# maus-blenano2-mk-1_1_0.net
KiCad netlist of a schematic drawn in EAGLE
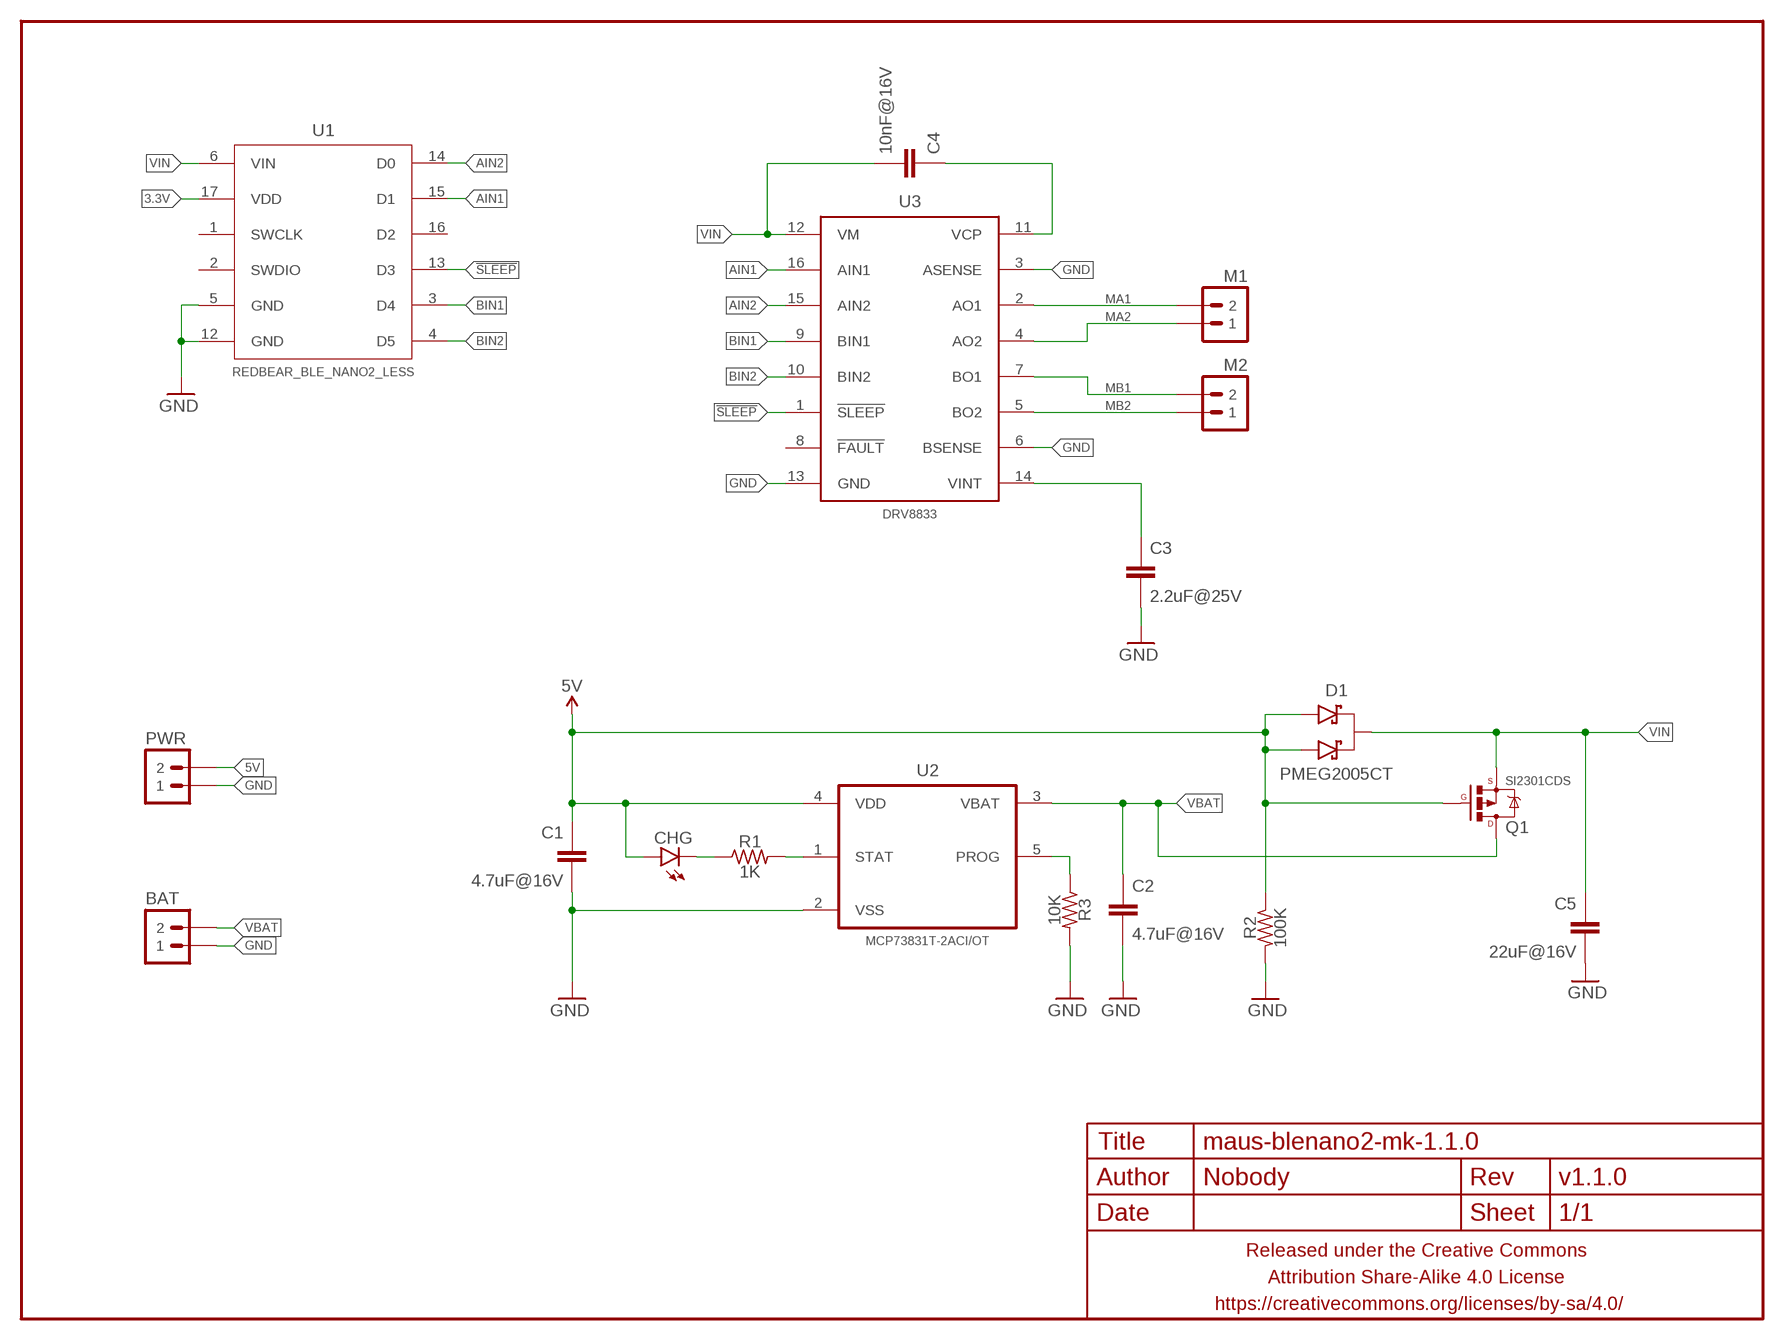
[diagram p0: schematic, sheet 1]

(export (version "E")
  (design (tool "Eeschema 10.0.6"))
  (components
    (comp (ref "BAT")
      (value "M02PTH-2MM")
      (footprint "eagle-import:1X02-2MM-PTH")
      (libsource (lib "eagle-import") (part "M02PTH-2MM"))
    )
    (comp (ref "C1")
      (value "4.7uF@16V")
      (footprint "eagle-import:C0603-TIGHTER")
      (libsource (lib "eagle-import") (part "CAPACITOR-CERAMICC0603-TIGHTER"))
    )
    (comp (ref "C2")
      (value "4.7uF@16V")
      (footprint "eagle-import:C0603-TIGHTER")
      (libsource (lib "eagle-import") (part "CAPACITOR-CERAMICC0603-TIGHTER"))
    )
    (comp (ref "C3")
      (value "2.2uF@25V")
      (footprint "eagle-import:C0603")
      (libsource (lib "eagle-import") (part "CAPACITOR-CERAMICC0603"))
    )
    (comp (ref "C4")
      (value "10nF@16V")
      (footprint "eagle-import:C0402")
      (libsource (lib "eagle-import") (part "CAPACITOR-CERAMICC0402"))
    )
    (comp (ref "C5")
      (value "22uF@16V")
      (footprint "eagle-import:C1206")
      (libsource (lib "eagle-import") (part "CAPACITOR-CERAMICC1206"))
    )
    (comp (ref "CHG")
      (value "LED0603-TIGHT")
      (footprint "eagle-import:LED-0603-TIGHT")
      (libsource (lib "eagle-import") (part "LED0603-TIGHT"))
    )
    (comp (ref "D1")
      (value "PMEG2005CT")
      (footprint "eagle-import:SOT23")
      (libsource (lib "eagle-import") (part "DIODE-SCHOTTKY-DUALPMEG2005CT"))
    )
    (comp (ref "FRAME1")
      (value "FRAME-LETTERNO_PACKAGE")
      (footprint "eagle-import:DUMMY")
      (fields (field (name "VERSION") "v1.1.0") (field (name "DESIGNER") "Nobody"))
      (libsource (lib "eagle-import") (part "FRAME-LETTERNO_PACKAGE"))
    )
    (comp (ref "M1")
      (value "M02PTH-2MM")
      (footprint "eagle-import:1X02-2MM-PTH")
      (libsource (lib "eagle-import") (part "M02PTH-2MM"))
    )
    (comp (ref "M2")
      (value "M02PTH-2MM")
      (footprint "eagle-import:1X02-2MM-PTH")
      (libsource (lib "eagle-import") (part "M02PTH-2MM"))
    )
    (comp (ref "PWR")
      (value "M02PTH-2MM")
      (footprint "eagle-import:1X02-2MM-PTH")
      (libsource (lib "eagle-import") (part "M02PTH-2MM"))
    )
    (comp (ref "Q1")
      (value "SI2301CDS")
      (footprint "eagle-import:SOT23")
      (libsource (lib "eagle-import") (part "MOSFET-PCHANNELSOT-23"))
    )
    (comp (ref "R1")
      (value "1K")
      (footprint "eagle-import:R0603-TIGHTER")
      (libsource (lib "eagle-import") (part "RESISTORR0603-TIGHTER"))
    )
    (comp (ref "R2")
      (value "100K")
      (footprint "eagle-import:R0603-TIGHTER")
      (libsource (lib "eagle-import") (part "RESISTORR0603-TIGHTER"))
    )
    (comp (ref "R3")
      (value "10K")
      (footprint "eagle-import:R0603-TIGHTER")
      (libsource (lib "eagle-import") (part "RESISTORR0603-TIGHTER"))
    )
    (comp (ref "U1")
      (value "REDBEAR_BLE_NANO2_LESS")
      (footprint "eagle-import:REDBEAR_BLE_NANO2_LESS")
      (libsource (lib "eagle-import") (part "REDBEAR_BLE_NANO2_LESS"))
    )
    (comp (ref "U2")
      (value "MCP73831T-2ACI/OT")
      (footprint "eagle-import:SOT95P280X145-5N")
      (libsource (lib "eagle-import") (part "MCP73831T-2ACI/OT"))
    )
    (comp (ref "U3")
      (value "DRV8833")
      (footprint "eagle-import:TSSOP16")
      (libsource (lib "eagle-import") (part "DRV8833PW"))
    )
  )
  (nets
    (net (code "1") (name "/MA1") (class "Default")
      (node (ref "M1") (pin "P$2") (pinfunction "2_P$2") (pintype "passive"))
      (node (ref "U3") (pin "2") (pinfunction "AO1_2") (pintype "bidirectional"))
    )
    (net (code "2") (name "/MA2") (class "Default")
      (node (ref "M1") (pin "P$1") (pinfunction "1_P$1") (pintype "passive"))
      (node (ref "U3") (pin "4") (pinfunction "AO2_4") (pintype "bidirectional"))
    )
    (net (code "3") (name "/MB1") (class "Default")
      (node (ref "M2") (pin "P$2") (pinfunction "2_P$2") (pintype "passive"))
      (node (ref "U3") (pin "7") (pinfunction "BO1_7") (pintype "bidirectional"))
    )
    (net (code "4") (name "/MB2") (class "Default")
      (node (ref "M2") (pin "P$1") (pinfunction "1_P$1") (pintype "passive"))
      (node (ref "U3") (pin "5") (pinfunction "BO2_5") (pintype "bidirectional"))
    )
    (net (code "5") (name "/~{SLEEP}") (class "Default")
      (node (ref "U1") (pin "13") (pinfunction "D3_13") (pintype "bidirectional"))
      (node (ref "U3") (pin "1") (pinfunction "~{SLEEP}_1") (pintype "input"))
    )
    (net (code "6") (name "3.3V") (class "Default")
      (node (ref "U1") (pin "17") (pinfunction "VDD_17") (pintype "bidirectional"))
    )
    (net (code "7") (name "5V") (class "Default")
      (node (ref "C1") (pin "1") (pinfunction "1_1") (pintype "passive"))
      (node (ref "CHG") (pin "A") (pinfunction "A_A") (pintype "passive"))
      (node (ref "D1") (pin "1") (pinfunction "A1_1") (pintype "passive"))
      (node (ref "D1") (pin "2") (pinfunction "A2_2") (pintype "passive"))
      (node (ref "PWR") (pin "P$2") (pinfunction "2_P$2") (pintype "passive"))
      (node (ref "Q1") (pin "1") (pinfunction "G_1") (pintype "passive"))
      (node (ref "R2") (pin "1") (pinfunction "1_1") (pintype "passive"))
      (node (ref "U2") (pin "4") (pinfunction "VDD_4") (pintype "power_in"))
    )
    (net (code "8") (name "AIN1") (class "Default")
      (node (ref "U1") (pin "15") (pinfunction "D1_15") (pintype "bidirectional"))
      (node (ref "U3") (pin "16") (pinfunction "AIN1_16") (pintype "input"))
    )
    (net (code "9") (name "AIN2") (class "Default")
      (node (ref "U1") (pin "14") (pinfunction "D0_14") (pintype "bidirectional"))
      (node (ref "U3") (pin "15") (pinfunction "AIN2_15") (pintype "input"))
    )
    (net (code "10") (name "BIN1") (class "Default")
      (node (ref "U1") (pin "3") (pinfunction "D4_3") (pintype "bidirectional"))
      (node (ref "U3") (pin "9") (pinfunction "BIN1_9") (pintype "input"))
    )
    (net (code "11") (name "BIN2") (class "Default")
      (node (ref "U1") (pin "4") (pinfunction "D5_4") (pintype "bidirectional"))
      (node (ref "U3") (pin "10") (pinfunction "BIN2_10") (pintype "input"))
    )
    (net (code "12") (name "GND") (class "Default")
      (node (ref "BAT") (pin "P$1") (pinfunction "1_P$1") (pintype "passive"))
      (node (ref "C1") (pin "2") (pinfunction "2_2") (pintype "passive"))
      (node (ref "C2") (pin "2") (pinfunction "2_2") (pintype "passive"))
      (node (ref "C3") (pin "2") (pinfunction "2_2") (pintype "passive"))
      (node (ref "C5") (pin "2") (pinfunction "2_2") (pintype "passive"))
      (node (ref "PWR") (pin "P$1") (pinfunction "1_P$1") (pintype "passive"))
      (node (ref "R2") (pin "2") (pinfunction "2_2") (pintype "passive"))
      (node (ref "R3") (pin "2") (pinfunction "2_2") (pintype "passive"))
      (node (ref "U1") (pin "12") (pinfunction "GND_12") (pintype "bidirectional"))
      (node (ref "U1") (pin "5") (pinfunction "GND_5") (pintype "bidirectional"))
      (node (ref "U2") (pin "2") (pinfunction "VSS_2") (pintype "power_in"))
      (node (ref "U3") (pin "13") (pinfunction "GND_13") (pintype "bidirectional"))
      (node (ref "U3") (pin "3") (pinfunction "ASENSE_3") (pintype "bidirectional"))
      (node (ref "U3") (pin "6") (pinfunction "BSENSE_6") (pintype "bidirectional"))
    )
    (net (code "13") (name "Net-(CHG-PadC)") (class "Default")
      (node (ref "CHG") (pin "C") (pinfunction "C_C") (pintype "passive"))
      (node (ref "R1") (pin "1") (pinfunction "1_1") (pintype "passive"))
    )
    (net (code "14") (name "Net-(U2-PROG)") (class "Default")
      (node (ref "R3") (pin "1") (pinfunction "1_1") (pintype "passive"))
      (node (ref "U2") (pin "5") (pinfunction "PROG_5") (pintype "input"))
    )
    (net (code "15") (name "Net-(U2-STAT)") (class "Default")
      (node (ref "R1") (pin "2") (pinfunction "2_2") (pintype "passive"))
      (node (ref "U2") (pin "1") (pinfunction "STAT_1") (pintype "output"))
    )
    (net (code "16") (name "Net-(U3-VCP)") (class "Default")
      (node (ref "C4") (pin "1") (pinfunction "1_1") (pintype "passive"))
      (node (ref "U3") (pin "11") (pinfunction "VCP_11") (pintype "bidirectional"))
    )
    (net (code "17") (name "Net-(U3-VINT)") (class "Default")
      (node (ref "C3") (pin "1") (pinfunction "1_1") (pintype "passive"))
      (node (ref "U3") (pin "14") (pinfunction "VINT_14") (pintype "bidirectional"))
    )
    (net (code "18") (name "VBAT") (class "Default")
      (node (ref "BAT") (pin "P$2") (pinfunction "2_P$2") (pintype "passive"))
      (node (ref "C2") (pin "1") (pinfunction "1_1") (pintype "passive"))
      (node (ref "Q1") (pin "3") (pinfunction "D_3") (pintype "passive"))
      (node (ref "U2") (pin "3") (pinfunction "VBAT_3") (pintype "output"))
    )
    (net (code "19") (name "VIN") (class "Default")
      (node (ref "C4") (pin "2") (pinfunction "2_2") (pintype "passive"))
      (node (ref "C5") (pin "1") (pinfunction "1_1") (pintype "passive"))
      (node (ref "D1") (pin "3") (pinfunction "K_3") (pintype "passive"))
      (node (ref "Q1") (pin "2") (pinfunction "S_2") (pintype "passive"))
      (node (ref "U1") (pin "6") (pinfunction "VIN_6") (pintype "bidirectional"))
      (node (ref "U3") (pin "12") (pinfunction "VM_12") (pintype "bidirectional"))
    )
    (net (code "20") (name "unconnected-(U1-D2-Pad16)") (class "Default")
      (node (ref "U1") (pin "16") (pinfunction "D2_16") (pintype "bidirectional"))
    )
    (net (code "21") (name "unconnected-(U1-SWCLK-Pad1)") (class "Default")
      (node (ref "U1") (pin "1") (pinfunction "SWCLK_1") (pintype "bidirectional"))
    )
    (net (code "22") (name "unconnected-(U1-SWDIO-Pad2)") (class "Default")
      (node (ref "U1") (pin "2") (pinfunction "SWDIO_2") (pintype "bidirectional"))
    )
    (net (code "23") (name "unconnected-(U3-~{FAULT}-Pad8)") (class "Default")
      (node (ref "U3") (pin "8") (pinfunction "~{FAULT}_8") (pintype "output"))
    )
  )
)
